# Camera.net
KiCad netlist of a schematic drawn in EAGLE
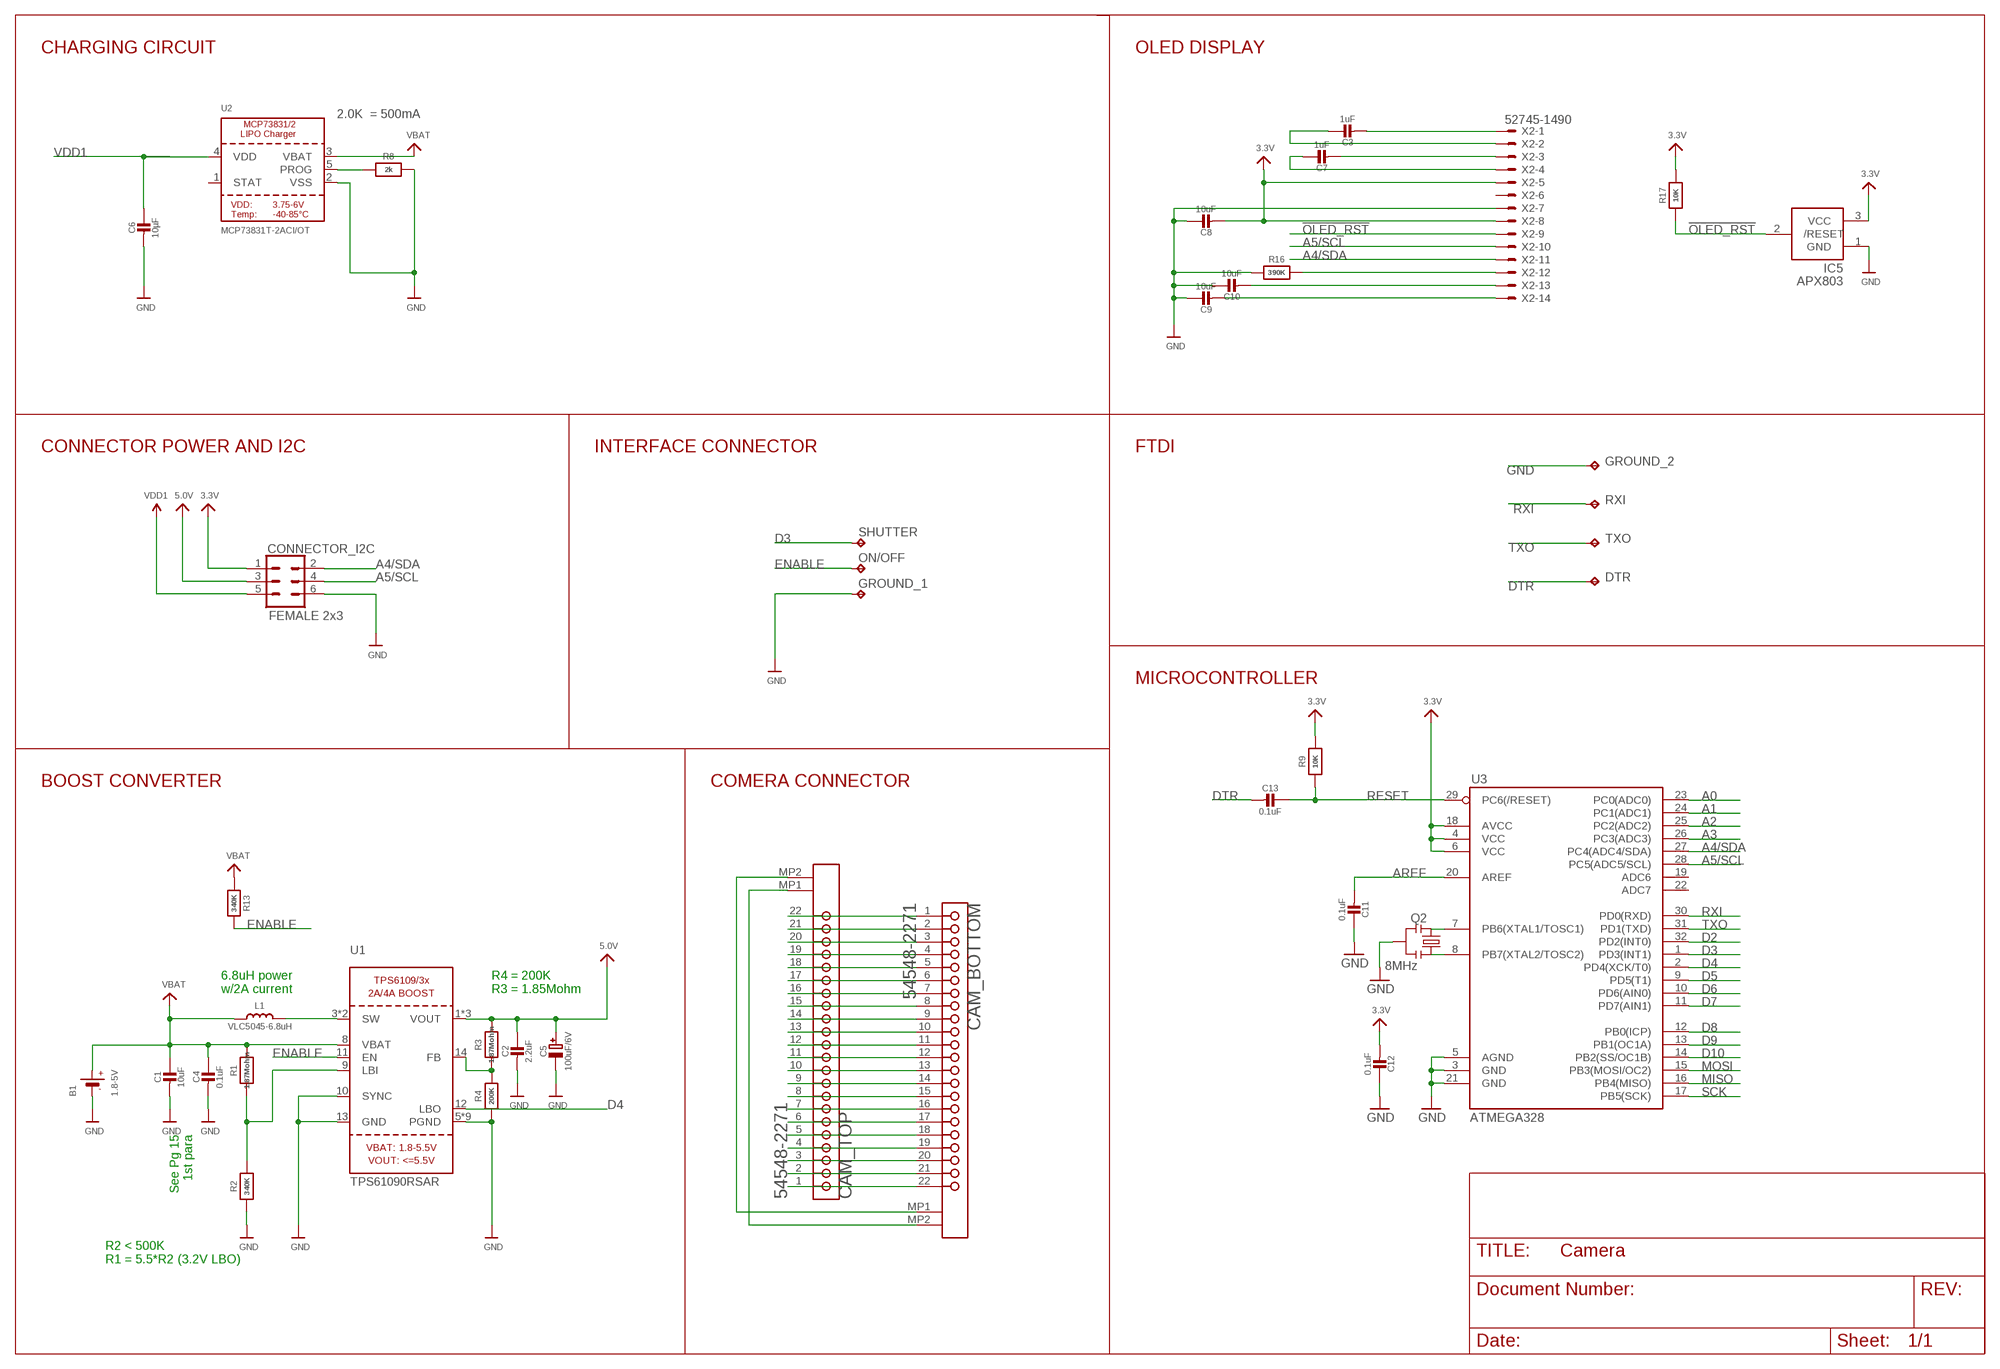
[diagram p0: schematic, sheet 1]

(export (version "E")
  (design (tool "Eeschema 10.0.6"))
  (components
    (comp (ref "B1")
      (value "1.8-5V")
      (footprint "eagle-import:JSTPH2")
      (libsource (lib "eagle-import") (part "BATTERY"))
    )
    (comp (ref "C1")
      (value "10uF")
      (footprint "eagle-import:0805-NO")
      (libsource (lib "eagle-import") (part "CAP_CERAMIC0805-NOOUTLINE"))
    )
    (comp (ref "C2")
      (value "2.2uF")
      (footprint "eagle-import:0805-NO")
      (libsource (lib "eagle-import") (part "CAP_CERAMIC0805-NOOUTLINE"))
    )
    (comp (ref "C3")
      (value "1uF")
      (footprint "eagle-import:0805-NO")
      (libsource (lib "eagle-import") (part "CAP_CERAMIC0805-NOOUTLINE"))
    )
    (comp (ref "C4")
      (value "0.1uF")
      (footprint "eagle-import:0805-NO")
      (libsource (lib "eagle-import") (part "CAP_CERAMIC0805-NOOUTLINE"))
    )
    (comp (ref "C5")
      (value "100uF/6V")
      (footprint "eagle-import:EIA3528-21_B-R")
      (libsource (lib "eagle-import") (part "CAP_TANTALUMB/3528_REFLOW"))
    )
    (comp (ref "C6")
      (value "10µF")
      (footprint "eagle-import:0805-NO")
      (libsource (lib "eagle-import") (part "CAP_CERAMIC0805-NOOUTLINE"))
    )
    (comp (ref "C7")
      (value "1uF")
      (footprint "eagle-import:0805-NO")
      (libsource (lib "eagle-import") (part "CAP_CERAMIC0805-NOOUTLINE"))
    )
    (comp (ref "C8")
      (value "10uF")
      (footprint "eagle-import:0805-NO")
      (libsource (lib "eagle-import") (part "CAP_CERAMIC0805-NOOUTLINE"))
    )
    (comp (ref "C9")
      (value "10uF")
      (footprint "eagle-import:0805-NO")
      (libsource (lib "eagle-import") (part "CAP_CERAMIC0805-NOOUTLINE"))
    )
    (comp (ref "C10")
      (value "10uF")
      (footprint "eagle-import:0805-NO")
      (libsource (lib "eagle-import") (part "CAP_CERAMIC0805-NOOUTLINE"))
    )
    (comp (ref "C11")
      (value "0.1uF")
      (footprint "eagle-import:0805-NO")
      (libsource (lib "eagle-import") (part "CAP_CERAMIC0805-NOOUTLINE"))
    )
    (comp (ref "C12")
      (value "0.1uF")
      (footprint "eagle-import:0805-NO")
      (libsource (lib "eagle-import") (part "CAP_CERAMIC0805-NOOUTLINE"))
    )
    (comp (ref "C13")
      (value "0.1uF")
      (footprint "eagle-import:0805-NO")
      (libsource (lib "eagle-import") (part "CAP_CERAMIC0805-NOOUTLINE"))
    )
    (comp (ref "CAM_BOTTOM")
      (value "MOLEX_54548-2271MOLEX_54548-2271_0_0")
      (footprint "eagle-import:MOLEX_54548-2271_0")
      (fields (field (name "MF") "Molex") (field (name "MPN") "54548-2271"))
      (libsource (lib "eagle-import") (part "MOLEX_54548-2271MOLEX_54548-2271_0_0"))
    )
    (comp (ref "CAM_TOP")
      (value "MOLEX_54548-2271MOLEX_54548-2271_0_0")
      (footprint "eagle-import:MOLEX_54548-2271_0")
      (fields (field (name "MF") "Molex") (field (name "MPN") "54548-2271"))
      (libsource (lib "eagle-import") (part "MOLEX_54548-2271MOLEX_54548-2271_0_0"))
    )
    (comp (ref "CONNECTOR_I2C")
      (value "FEMALE 2x3")
      (footprint "eagle-import:2X3")
      (libsource (lib "eagle-import") (part "CONN_03X2FEMALE"))
    )
    (comp (ref "DTR")
      (value "TPB1,27")
      (footprint "eagle-import:B1,27")
      (libsource (lib "eagle-import") (part "TPB1,27"))
    )
    (comp (ref "GROUND_1")
      (value "TPB1,27")
      (footprint "eagle-import:B1,27")
      (libsource (lib "eagle-import") (part "TPB1,27"))
    )
    (comp (ref "GROUND_2")
      (value "TPB1,27")
      (footprint "eagle-import:B1,27")
      (libsource (lib "eagle-import") (part "TPB1,27"))
    )
    (comp (ref "IC5")
      (value "APX803")
      (footprint "eagle-import:SOT23")
      (libsource (lib "eagle-import") (part "AXP083-SAG"))
    )
    (comp (ref "L1")
      (value "VLC5045-6.8uH")
      (footprint "eagle-import:INDUCTOR_5X5MM_TDK_VLC5045")
      (libsource (lib "eagle-import") (part "INDUCTORTDK_VLC5045"))
    )
    (comp (ref "ON/OFF")
      (value "TPB1,27")
      (footprint "eagle-import:B1,27")
      (libsource (lib "eagle-import") (part "TPB1,27"))
    )
    (comp (ref "Q2")
      (value "8MHz")
      (footprint "eagle-import:RESONATOR-SMD")
      (libsource (lib "eagle-import") (part "RESONATORSMD"))
    )
    (comp (ref "R1")
      (value "1.87Mohm")
      (footprint "eagle-import:0805-NO")
      (libsource (lib "eagle-import") (part "RESISTOR0805_NOOUTLINE"))
    )
    (comp (ref "R2")
      (value "340K")
      (footprint "eagle-import:0805-NO")
      (libsource (lib "eagle-import") (part "RESISTOR0805_NOOUTLINE"))
    )
    (comp (ref "R3")
      (value "1.87Mohm")
      (footprint "eagle-import:0805-NO")
      (libsource (lib "eagle-import") (part "RESISTOR0805_NOOUTLINE"))
    )
    (comp (ref "R4")
      (value "200K")
      (footprint "eagle-import:0805-NO")
      (libsource (lib "eagle-import") (part "RESISTOR0805_NOOUTLINE"))
    )
    (comp (ref "R8")
      (value "2k")
      (footprint "eagle-import:0805-NO")
      (libsource (lib "eagle-import") (part "RESISTOR0805_NOOUTLINE"))
    )
    (comp (ref "R9")
      (value "10K")
      (footprint "eagle-import:0805-NO")
      (libsource (lib "eagle-import") (part "RESISTOR0805_NOOUTLINE"))
    )
    (comp (ref "R13")
      (value "340K")
      (footprint "eagle-import:0805-NO")
      (libsource (lib "eagle-import") (part "RESISTOR0805_NOOUTLINE"))
    )
    (comp (ref "R16")
      (value "390K")
      (footprint "eagle-import:0805-NO")
      (libsource (lib "eagle-import") (part "RESISTOR0805_NOOUTLINE"))
    )
    (comp (ref "R17")
      (value "10K")
      (footprint "eagle-import:0805-NO")
      (libsource (lib "eagle-import") (part "RESISTOR0805_NOOUTLINE"))
    )
    (comp (ref "RXI")
      (value "TPB1,27")
      (footprint "eagle-import:B1,27")
      (libsource (lib "eagle-import") (part "TPB1,27"))
    )
    (comp (ref "SHUTTER")
      (value "TPB1,27")
      (footprint "eagle-import:B1,27")
      (libsource (lib "eagle-import") (part "TPB1,27"))
    )
    (comp (ref "TXO")
      (value "TPB1,27")
      (footprint "eagle-import:B1,27")
      (libsource (lib "eagle-import") (part "TPB1,27"))
    )
    (comp (ref "U1")
      (value "TPS61090RSAR")
      (footprint "eagle-import:PVQFN-16")
      (libsource (lib "eagle-import") (part "VREG_TPS6103X"))
    )
    (comp (ref "U2")
      (value "MCP73831T-2ACI/OT")
      (footprint "eagle-import:SOT23-5")
      (libsource (lib "eagle-import") (part "MCP73831/2"))
    )
    (comp (ref "U3")
      (value "ATMEGA328")
      (footprint "eagle-import:TQFP32-08")
      (libsource (lib "eagle-import") (part "ATMEGA168"))
    )
    (comp (ref "X2")
      (value "52745-1490")
      (footprint "eagle-import:52745-1490")
      (fields (field (name "MF") "WALDOM/MOLEX"))
      (libsource (lib "eagle-import") (part "52745-1490"))
    )
  )
  (nets
    (net (code "1") (name "/A0") (class "Default")
      (node (ref "U3") (pin "23") (pinfunction "PC0(ADC0)_23") (pintype "bidirectional"))
    )
    (net (code "2") (name "/A1") (class "Default")
      (node (ref "U3") (pin "24") (pinfunction "PC1(ADC1)_24") (pintype "bidirectional"))
    )
    (net (code "3") (name "/A2") (class "Default")
      (node (ref "U3") (pin "25") (pinfunction "PC2(ADC2)_25") (pintype "bidirectional"))
    )
    (net (code "4") (name "/A3") (class "Default")
      (node (ref "U3") (pin "26") (pinfunction "PC3(ADC3)_26") (pintype "bidirectional"))
    )
    (net (code "5") (name "/A4{slash}SDA") (class "Default")
      (node (ref "CONNECTOR_I2C") (pin "2") (pinfunction "2_2") (pintype "bidirectional"))
      (node (ref "U3") (pin "27") (pinfunction "PC4(ADC4/SDA)_27") (pintype "bidirectional"))
      (node (ref "X2") (pin "11") (pinfunction "S_11") (pintype "passive"))
    )
    (net (code "6") (name "/A5{slash}SCL") (class "Default")
      (node (ref "CONNECTOR_I2C") (pin "4") (pinfunction "4_4") (pintype "bidirectional"))
      (node (ref "U3") (pin "28") (pinfunction "PC5(ADC5/SCL)_28") (pintype "bidirectional"))
      (node (ref "X2") (pin "10") (pinfunction "S_10") (pintype "passive"))
    )
    (net (code "7") (name "/AREF") (class "Default")
      (node (ref "C11") (pin "2") (pinfunction "2_2") (pintype "passive"))
      (node (ref "U3") (pin "20") (pinfunction "AREF_20") (pintype "bidirectional"))
    )
    (net (code "8") (name "/D2") (class "Default")
      (node (ref "U3") (pin "32") (pinfunction "PD2(INT0)_32") (pintype "bidirectional"))
    )
    (net (code "9") (name "/D3") (class "Default")
      (node (ref "SHUTTER") (pin "TP") (pinfunction "TP_TP") (pintype "input"))
      (node (ref "U3") (pin "1") (pinfunction "PD3(INT1)_1") (pintype "bidirectional"))
    )
    (net (code "10") (name "/D4") (class "Default")
      (node (ref "U1") (pin "12") (pinfunction "LBO_12") (pintype "output"))
      (node (ref "U3") (pin "2") (pinfunction "PD4(XCK/T0)_2") (pintype "bidirectional"))
    )
    (net (code "11") (name "/D5") (class "Default")
      (node (ref "U3") (pin "9") (pinfunction "PD5(T1)_9") (pintype "bidirectional"))
    )
    (net (code "12") (name "/D6") (class "Default")
      (node (ref "U3") (pin "10") (pinfunction "PD6(AIN0)_10") (pintype "bidirectional"))
    )
    (net (code "13") (name "/D7") (class "Default")
      (node (ref "U3") (pin "11") (pinfunction "PD7(AIN1)_11") (pintype "bidirectional"))
    )
    (net (code "14") (name "/D8") (class "Default")
      (node (ref "U3") (pin "12") (pinfunction "PB0(ICP)_12") (pintype "bidirectional"))
    )
    (net (code "15") (name "/D9") (class "Default")
      (node (ref "U3") (pin "13") (pinfunction "PB1(OC1A)_13") (pintype "bidirectional"))
    )
    (net (code "16") (name "/D10") (class "Default")
      (node (ref "U3") (pin "14") (pinfunction "PB2(SS/OC1B)_14") (pintype "bidirectional"))
    )
    (net (code "17") (name "/DTR") (class "Default")
      (node (ref "C13") (pin "2") (pinfunction "2_2") (pintype "passive"))
      (node (ref "DTR") (pin "TP") (pinfunction "TP_TP") (pintype "input"))
    )
    (net (code "18") (name "/ENABLE") (class "Default")
      (node (ref "ON/OFF") (pin "TP") (pinfunction "TP_TP") (pintype "input"))
      (node (ref "R13") (pin "2") (pinfunction "2_2") (pintype "passive"))
      (node (ref "U1") (pin "11") (pinfunction "EN_11") (pintype "input"))
    )
    (net (code "19") (name "/MISO") (class "Default")
      (node (ref "U3") (pin "16") (pinfunction "PB4(MISO)_16") (pintype "bidirectional"))
    )
    (net (code "20") (name "/MOSI") (class "Default")
      (node (ref "U3") (pin "15") (pinfunction "PB3(MOSI/OC2)_15") (pintype "bidirectional"))
    )
    (net (code "21") (name "/RESET") (class "Default")
      (node (ref "C13") (pin "1") (pinfunction "1_1") (pintype "passive"))
      (node (ref "R9") (pin "1") (pinfunction "1_1") (pintype "passive"))
      (node (ref "U3") (pin "29") (pinfunction "PC6(/RESET)_29") (pintype "bidirectional"))
    )
    (net (code "22") (name "/RXI") (class "Default")
      (node (ref "RXI") (pin "TP") (pinfunction "TP_TP") (pintype "input"))
      (node (ref "U3") (pin "30") (pinfunction "PD0(RXD)_30") (pintype "bidirectional"))
    )
    (net (code "23") (name "/SCK") (class "Default")
      (node (ref "U3") (pin "17") (pinfunction "PB5(SCK)_17") (pintype "bidirectional"))
    )
    (net (code "24") (name "/TXO") (class "Default")
      (node (ref "TXO") (pin "TP") (pinfunction "TP_TP") (pintype "input"))
      (node (ref "U3") (pin "31") (pinfunction "PD1(TXD)_31") (pintype "bidirectional"))
    )
    (net (code "25") (name "/~{OLED_RST}") (class "Default")
      (node (ref "IC5") (pin "2") (pinfunction "/RESET_2") (pintype "output"))
      (node (ref "R17") (pin "1") (pinfunction "1_1") (pintype "passive"))
      (node (ref "X2") (pin "9") (pinfunction "S_9") (pintype "passive"))
    )
    (net (code "26") (name "3.3V") (class "Default")
      (node (ref "C12") (pin "2") (pinfunction "2_2") (pintype "passive"))
      (node (ref "C8") (pin "2") (pinfunction "2_2") (pintype "passive"))
      (node (ref "CONNECTOR_I2C") (pin "1") (pinfunction "1_1") (pintype "bidirectional"))
      (node (ref "IC5") (pin "3") (pinfunction "VCC_3") (pintype "power_in"))
      (node (ref "R17") (pin "2") (pinfunction "2_2") (pintype "passive"))
      (node (ref "R9") (pin "2") (pinfunction "2_2") (pintype "passive"))
      (node (ref "U3") (pin "18") (pinfunction "AVCC_18") (pintype "bidirectional"))
      (node (ref "U3") (pin "4") (pinfunction "VCC_4") (pintype "bidirectional"))
      (node (ref "U3") (pin "6") (pinfunction "VCC_6") (pintype "bidirectional"))
      (node (ref "X2") (pin "5") (pinfunction "S_5") (pintype "passive"))
      (node (ref "X2") (pin "8") (pinfunction "S_8") (pintype "passive"))
    )
    (net (code "27") (name "5.0V") (class "Default")
      (node (ref "C2") (pin "1") (pinfunction "1_1") (pintype "passive"))
      (node (ref "C5") (pin "+") (pinfunction "+_+") (pintype "passive"))
      (node (ref "CONNECTOR_I2C") (pin "3") (pinfunction "3_3") (pintype "bidirectional"))
      (node (ref "R3") (pin "2") (pinfunction "2_2") (pintype "passive"))
      (node (ref "U1") (pin "1") (pinfunction "VOUT_1") (pintype "power_in"))
      (node (ref "U1") (pin "15") (pinfunction "VOUT_15") (pintype "power_in"))
      (node (ref "U1") (pin "16") (pinfunction "VOUT_16") (pintype "power_in"))
    )
    (net (code "28") (name "GND") (class "Default")
      (node (ref "B1") (pin "1") (pinfunction "-_1") (pintype "passive"))
      (node (ref "C1") (pin "2") (pinfunction "2_2") (pintype "passive"))
      (node (ref "C10") (pin "1") (pinfunction "1_1") (pintype "passive"))
      (node (ref "C11") (pin "1") (pinfunction "1_1") (pintype "passive"))
      (node (ref "C12") (pin "1") (pinfunction "1_1") (pintype "passive"))
      (node (ref "C2") (pin "2") (pinfunction "2_2") (pintype "passive"))
      (node (ref "C4") (pin "2") (pinfunction "2_2") (pintype "passive"))
      (node (ref "C5") (pin "-") (pinfunction "-_-") (pintype "passive"))
      (node (ref "C6") (pin "2") (pinfunction "2_2") (pintype "passive"))
      (node (ref "C8") (pin "1") (pinfunction "1_1") (pintype "passive"))
      (node (ref "C9") (pin "1") (pinfunction "1_1") (pintype "passive"))
      (node (ref "CONNECTOR_I2C") (pin "6") (pinfunction "6_6") (pintype "bidirectional"))
      (node (ref "GROUND_1") (pin "TP") (pinfunction "TP_TP") (pintype "input"))
      (node (ref "GROUND_2") (pin "TP") (pinfunction "TP_TP") (pintype "input"))
      (node (ref "IC5") (pin "1") (pinfunction "GND_1") (pintype "power_in"))
      (node (ref "Q2") (pin "2") (pinfunction "2_2") (pintype "passive"))
      (node (ref "R16") (pin "1") (pinfunction "1_1") (pintype "passive"))
      (node (ref "R2") (pin "1") (pinfunction "1_1") (pintype "passive"))
      (node (ref "R4") (pin "1") (pinfunction "1_1") (pintype "passive"))
      (node (ref "R8") (pin "2") (pinfunction "2_2") (pintype "passive"))
      (node (ref "U1") (pin "10") (pinfunction "SYNC_10") (pintype "input"))
      (node (ref "U1") (pin "13") (pinfunction "GND_13") (pintype "power_in"))
      (node (ref "U1") (pin "5") (pinfunction "PGND_5") (pintype "power_in"))
      (node (ref "U1") (pin "6") (pinfunction "PGND_6") (pintype "power_in"))
      (node (ref "U1") (pin "7") (pinfunction "PGND_7") (pintype "power_in"))
      (node (ref "U1") (pin "P$18") (pinfunction "PGND_P$18") (pintype "power_in"))
      (node (ref "U1") (pin "P$19") (pinfunction "PGND_P$19") (pintype "power_in"))
      (node (ref "U1") (pin "P$20") (pinfunction "PGND_P$20") (pintype "power_in"))
      (node (ref "U1") (pin "P$21") (pinfunction "PGND_P$21") (pintype "power_in"))
      (node (ref "U1") (pin "P$22") (pinfunction "PGND_P$22") (pintype "power_in"))
      (node (ref "U1") (pin "THERMAL") (pinfunction "PGND_THERMAL") (pintype "power_in"))
      (node (ref "U2") (pin "2") (pinfunction "VSS_2") (pintype "power_in"))
      (node (ref "U3") (pin "21") (pinfunction "GND_21") (pintype "bidirectional"))
      (node (ref "U3") (pin "3") (pinfunction "GND_3") (pintype "bidirectional"))
      (node (ref "U3") (pin "5") (pinfunction "AGND_5") (pintype "bidirectional"))
      (node (ref "X2") (pin "7") (pinfunction "S_7") (pintype "passive"))
    )
    (net (code "29") (name "Net-(CAM_BOTTOM-Pad1)") (class "Default")
      (node (ref "CAM_BOTTOM") (pin "1") (pinfunction "1_1") (pintype "passive"))
      (node (ref "CAM_TOP") (pin "22") (pinfunction "22_22") (pintype "passive"))
    )
    (net (code "30") (name "Net-(CAM_BOTTOM-Pad2)") (class "Default")
      (node (ref "CAM_BOTTOM") (pin "2") (pinfunction "2_2") (pintype "passive"))
      (node (ref "CAM_TOP") (pin "21") (pinfunction "21_21") (pintype "passive"))
    )
    (net (code "31") (name "Net-(CAM_BOTTOM-Pad3)") (class "Default")
      (node (ref "CAM_BOTTOM") (pin "3") (pinfunction "3_3") (pintype "passive"))
      (node (ref "CAM_TOP") (pin "20") (pinfunction "20_20") (pintype "passive"))
    )
    (net (code "32") (name "Net-(CAM_BOTTOM-Pad4)") (class "Default")
      (node (ref "CAM_BOTTOM") (pin "4") (pinfunction "4_4") (pintype "passive"))
      (node (ref "CAM_TOP") (pin "19") (pinfunction "19_19") (pintype "passive"))
    )
    (net (code "33") (name "Net-(CAM_BOTTOM-Pad5)") (class "Default")
      (node (ref "CAM_BOTTOM") (pin "5") (pinfunction "5_5") (pintype "passive"))
      (node (ref "CAM_TOP") (pin "18") (pinfunction "18_18") (pintype "passive"))
    )
    (net (code "34") (name "Net-(CAM_BOTTOM-Pad6)") (class "Default")
      (node (ref "CAM_BOTTOM") (pin "6") (pinfunction "6_6") (pintype "passive"))
      (node (ref "CAM_TOP") (pin "17") (pinfunction "17_17") (pintype "passive"))
    )
    (net (code "35") (name "Net-(CAM_BOTTOM-Pad7)") (class "Default")
      (node (ref "CAM_BOTTOM") (pin "7") (pinfunction "7_7") (pintype "passive"))
      (node (ref "CAM_TOP") (pin "16") (pinfunction "16_16") (pintype "passive"))
    )
    (net (code "36") (name "Net-(CAM_BOTTOM-Pad8)") (class "Default")
      (node (ref "CAM_BOTTOM") (pin "8") (pinfunction "8_8") (pintype "passive"))
      (node (ref "CAM_TOP") (pin "15") (pinfunction "15_15") (pintype "passive"))
    )
    (net (code "37") (name "Net-(CAM_BOTTOM-Pad9)") (class "Default")
      (node (ref "CAM_BOTTOM") (pin "9") (pinfunction "9_9") (pintype "passive"))
      (node (ref "CAM_TOP") (pin "14") (pinfunction "14_14") (pintype "passive"))
    )
    (net (code "38") (name "Net-(CAM_BOTTOM-Pad10)") (class "Default")
      (node (ref "CAM_BOTTOM") (pin "10") (pinfunction "10_10") (pintype "passive"))
      (node (ref "CAM_TOP") (pin "13") (pinfunction "13_13") (pintype "passive"))
    )
    (net (code "39") (name "Net-(CAM_BOTTOM-Pad11)") (class "Default")
      (node (ref "CAM_BOTTOM") (pin "11") (pinfunction "11_11") (pintype "passive"))
      (node (ref "CAM_TOP") (pin "12") (pinfunction "12_12") (pintype "passive"))
    )
    (net (code "40") (name "Net-(CAM_BOTTOM-Pad12)") (class "Default")
      (node (ref "CAM_BOTTOM") (pin "12") (pinfunction "12_12") (pintype "passive"))
      (node (ref "CAM_TOP") (pin "11") (pinfunction "11_11") (pintype "passive"))
    )
    (net (code "41") (name "Net-(CAM_BOTTOM-Pad13)") (class "Default")
      (node (ref "CAM_BOTTOM") (pin "13") (pinfunction "13_13") (pintype "passive"))
      (node (ref "CAM_TOP") (pin "10") (pinfunction "10_10") (pintype "passive"))
    )
    (net (code "42") (name "Net-(CAM_BOTTOM-Pad14)") (class "Default")
      (node (ref "CAM_BOTTOM") (pin "14") (pinfunction "14_14") (pintype "passive"))
      (node (ref "CAM_TOP") (pin "9") (pinfunction "9_9") (pintype "passive"))
    )
    (net (code "43") (name "Net-(CAM_BOTTOM-Pad15)") (class "Default")
      (node (ref "CAM_BOTTOM") (pin "15") (pinfunction "15_15") (pintype "passive"))
      (node (ref "CAM_TOP") (pin "8") (pinfunction "8_8") (pintype "passive"))
    )
    (net (code "44") (name "Net-(CAM_BOTTOM-Pad16)") (class "Default")
      (node (ref "CAM_BOTTOM") (pin "16") (pinfunction "16_16") (pintype "passive"))
      (node (ref "CAM_TOP") (pin "7") (pinfunction "7_7") (pintype "passive"))
    )
    (net (code "45") (name "Net-(CAM_BOTTOM-Pad17)") (class "Default")
      (node (ref "CAM_BOTTOM") (pin "17") (pinfunction "17_17") (pintype "passive"))
      (node (ref "CAM_TOP") (pin "6") (pinfunction "6_6") (pintype "passive"))
    )
    (net (code "46") (name "Net-(CAM_BOTTOM-Pad18)") (class "Default")
      (node (ref "CAM_BOTTOM") (pin "18") (pinfunction "18_18") (pintype "passive"))
      (node (ref "CAM_TOP") (pin "5") (pinfunction "5_5") (pintype "passive"))
    )
    (net (code "47") (name "Net-(CAM_BOTTOM-Pad19)") (class "Default")
      (node (ref "CAM_BOTTOM") (pin "19") (pinfunction "19_19") (pintype "passive"))
      (node (ref "CAM_TOP") (pin "4") (pinfunction "4_4") (pintype "passive"))
    )
    (net (code "48") (name "Net-(CAM_BOTTOM-Pad20)") (class "Default")
      (node (ref "CAM_BOTTOM") (pin "20") (pinfunction "20_20") (pintype "passive"))
      (node (ref "CAM_TOP") (pin "3") (pinfunction "3_3") (pintype "passive"))
    )
    (net (code "49") (name "Net-(CAM_BOTTOM-Pad21)") (class "Default")
      (node (ref "CAM_BOTTOM") (pin "21") (pinfunction "21_21") (pintype "passive"))
      (node (ref "CAM_TOP") (pin "2") (pinfunction "2_2") (pintype "passive"))
    )
    (net (code "50") (name "Net-(CAM_BOTTOM-Pad22)") (class "Default")
      (node (ref "CAM_BOTTOM") (pin "22") (pinfunction "22_22") (pintype "passive"))
      (node (ref "CAM_TOP") (pin "1") (pinfunction "1_1") (pintype "passive"))
    )
    (net (code "51") (name "Net-(CAM_BOTTOM-PadMP1)") (class "Default")
      (node (ref "CAM_BOTTOM") (pin "MP1") (pinfunction "MP1_MP1") (pintype "passive"))
      (node (ref "CAM_TOP") (pin "MP2") (pinfunction "MP2_MP2") (pintype "passive"))
    )
    (net (code "52") (name "Net-(CAM_BOTTOM-PadMP2)") (class "Default")
      (node (ref "CAM_BOTTOM") (pin "MP2") (pinfunction "MP2_MP2") (pintype "passive"))
      (node (ref "CAM_TOP") (pin "MP1") (pinfunction "MP1_MP1") (pintype "passive"))
    )
    (net (code "53") (name "Net-(L1-2)") (class "Default")
      (node (ref "L1") (pin "P$2") (pinfunction "2_P$2") (pintype "passive"))
      (node (ref "U1") (pin "3") (pinfunction "SW_3") (pintype "input"))
      (node (ref "U1") (pin "4") (pinfunction "SW_4") (pintype "input"))
    )
    (net (code "54") (name "Net-(U1-FB)") (class "Default")
      (node (ref "R3") (pin "1") (pinfunction "1_1") (pintype "passive"))
      (node (ref "R4") (pin "2") (pinfunction "2_2") (pintype "passive"))
      (node (ref "U1") (pin "14") (pinfunction "FB_14") (pintype "input"))
    )
    (net (code "55") (name "Net-(U1-LBI)") (class "Default")
      (node (ref "R1") (pin "1") (pinfunction "1_1") (pintype "passive"))
      (node (ref "R2") (pin "2") (pinfunction "2_2") (pintype "passive"))
      (node (ref "U1") (pin "9") (pinfunction "LBI_9") (pintype "input"))
    )
    (net (code "56") (name "Net-(U2-PROG)") (class "Default")
      (node (ref "R8") (pin "1") (pinfunction "1_1") (pintype "passive"))
      (node (ref "U2") (pin "5") (pinfunction "PROG_5") (pintype "input"))
    )
    (net (code "57") (name "Net-(U3-PB6(XTAL1{slash}TOSC1))") (class "Default")
      (node (ref "Q2") (pin "3") (pinfunction "3_3") (pintype "passive"))
      (node (ref "U3") (pin "7") (pinfunction "PB6(XTAL1/TOSC1)_7") (pintype "bidirectional"))
    )
    (net (code "58") (name "Net-(U3-PB7(XTAL2{slash}TOSC2))") (class "Default")
      (node (ref "Q2") (pin "1") (pinfunction "1_1") (pintype "passive"))
      (node (ref "U3") (pin "8") (pinfunction "PB7(XTAL2/TOSC2)_8") (pintype "bidirectional"))
    )
    (net (code "59") (name "Net-(X2A-S)") (class "Default")
      (node (ref "C3") (pin "2") (pinfunction "2_2") (pintype "passive"))
      (node (ref "X2") (pin "1") (pinfunction "S_1") (pintype "passive"))
    )
    (net (code "60") (name "Net-(X2D-S)") (class "Default")
      (node (ref "R16") (pin "2") (pinfunction "2_2") (pintype "passive"))
      (node (ref "X2") (pin "12") (pinfunction "S_12") (pintype "passive"))
    )
    (net (code "61") (name "Net-(X2E-S)") (class "Default")
      (node (ref "C10") (pin "2") (pinfunction "2_2") (pintype "passive"))
      (node (ref "X2") (pin "13") (pinfunction "S_13") (pintype "passive"))
    )
    (net (code "62") (name "Net-(X2F-S)") (class "Default")
      (node (ref "C9") (pin "2") (pinfunction "2_2") (pintype "passive"))
      (node (ref "X2") (pin "14") (pinfunction "S_14") (pintype "passive"))
    )
    (net (code "63") (name "Net-(X2G-S)") (class "Default")
      (node (ref "C3") (pin "1") (pinfunction "1_1") (pintype "passive"))
      (node (ref "X2") (pin "2") (pinfunction "S_2") (pintype "passive"))
    )
    (net (code "64") (name "Net-(X2H-S)") (class "Default")
      (node (ref "C7") (pin "2") (pinfunction "2_2") (pintype "passive"))
      (node (ref "X2") (pin "3") (pinfunction "S_3") (pintype "passive"))
    )
    (net (code "65") (name "Net-(X2I-S)") (class "Default")
      (node (ref "C7") (pin "1") (pinfunction "1_1") (pintype "passive"))
      (node (ref "X2") (pin "4") (pinfunction "S_4") (pintype "passive"))
    )
    (net (code "66") (name "VBAT") (class "Default")
      (node (ref "B1") (pin "2") (pinfunction "+_2") (pintype "passive"))
      (node (ref "C1") (pin "1") (pinfunction "1_1") (pintype "passive"))
      (node (ref "C4") (pin "1") (pinfunction "1_1") (pintype "passive"))
      (node (ref "L1") (pin "P$1") (pinfunction "1_P$1") (pintype "passive"))
      (node (ref "R1") (pin "2") (pinfunction "2_2") (pintype "passive"))
      (node (ref "R13") (pin "1") (pinfunction "1_1") (pintype "passive"))
      (node (ref "U1") (pin "8") (pinfunction "VBAT_8") (pintype "input"))
      (node (ref "U2") (pin "3") (pinfunction "VBAT_3") (pintype "power_in"))
    )
    (net (code "67") (name "VCC") (class "Default")
      (node (ref "C6") (pin "1") (pinfunction "1_1") (pintype "passive"))
      (node (ref "CONNECTOR_I2C") (pin "5") (pinfunction "5_5") (pintype "bidirectional"))
      (node (ref "U2") (pin "4") (pinfunction "VDD_4") (pintype "power_in"))
    )
    (net (code "68") (name "unconnected-(U2-STAT-Pad1)") (class "Default")
      (node (ref "U2") (pin "1") (pinfunction "STAT_1") (pintype "output"))
    )
    (net (code "69") (name "unconnected-(U3-ADC6-Pad19)") (class "Default")
      (node (ref "U3") (pin "19") (pinfunction "ADC6_19") (pintype "bidirectional"))
    )
    (net (code "70") (name "unconnected-(U3-ADC7-Pad22)") (class "Default")
      (node (ref "U3") (pin "22") (pinfunction "ADC7_22") (pintype "bidirectional"))
    )
    (net (code "71") (name "unconnected-(X2K-S-Pad6)") (class "Default")
      (node (ref "X2") (pin "6") (pinfunction "S_6") (pintype "passive"))
    )
  )
)
